# XBEE.net
KiCad netlist of a schematic drawn in Altium Designer
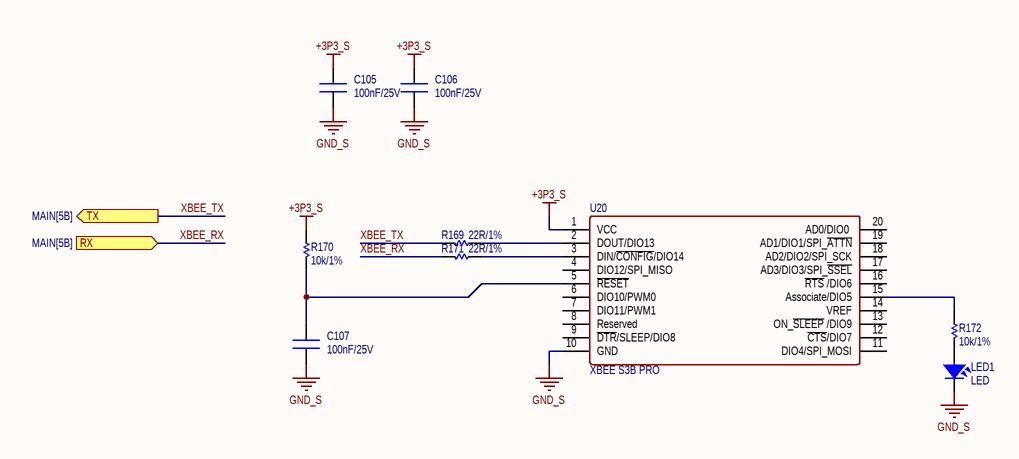
[diagram p0: XBEE.SchDoc]

(export (version "E")
  (design (tool "Eeschema 10.0.6"))
  (components
    (comp (ref "C105")
      (value "100nF/25V")
      (footprint "CN-SMD-0603")
      (description "CAP CER 0.1UF 25V X7R 0603")
      (libsource (lib "Library") (part "CN"))
    )
    (comp (ref "C106")
      (value "100nF/25V")
      (footprint "CN-SMD-0603")
      (description "CAP CER 0.1UF 25V X7R 0603")
      (libsource (lib "Library") (part "CN"))
    )
    (comp (ref "C107")
      (value "100nF/25V")
      (footprint "CN-SMD-0603")
      (description "CAP CER 0.1UF 25V X7R 0603")
      (libsource (lib "Library") (part "CN"))
    )
    (comp (ref "LED1")
      (value "LED")
      (footprint "LED-0603-RED")
      (description "LED RED CLEAR 0603 SMD")
      (libsource (lib "Library") (part "LED SMD"))
    )
    (comp (ref "R169")
      (value "22R/1%")
      (footprint "RES-SMD-0603")
      (description "RES SMD 22 OHM 1% 1/10W 0603")
      (libsource (lib "Library") (part "Res-SMD"))
    )
    (comp (ref "R170")
      (value "10k/1%")
      (footprint "RES-SMD-0603")
      (description "RES SMD 10K OHM 1% 1/10W 0603")
      (fields
        (field (name "MANUFACTURER") "Generic Components")
        (field (name "PUBLISHER") "Altium Hobart Technology Centre")
      )
      (libsource (lib "Library") (part "Res-SMD"))
    )
    (comp (ref "R171")
      (value "22R/1%")
      (footprint "RES-SMD-0603")
      (description "RES SMD 22 OHM 1% 1/10W 0603")
      (libsource (lib "Library") (part "Res-SMD"))
    )
    (comp (ref "R172")
      (value "10k/1%")
      (footprint "RES-SMD-0603")
      (description "RES SMD 10K OHM 1% 1/10W 0603")
      (fields
        (field (name "MANUFACTURER") "Generic Components")
        (field (name "PUBLISHER") "Altium Hobart Technology Centre")
      )
      (libsource (lib "Library") (part "Res-SMD"))
    )
    (comp (ref "U20")
      (value "XBEE S3B PRO")
      (footprint "XBEE S3B PRO DIP")
      (libsource (lib "Library") (part "XBEE S3B PRO"))
    )
  )
  (nets
    (net (code "1") (name "+3P3_S") (class "Default")
      (node (ref "C105") (pin "2") (pinfunction "2_2") (pintype "passive"))
      (node (ref "C106") (pin "2") (pinfunction "2_2") (pintype "passive"))
      (node (ref "R170") (pin "1") (pinfunction "1_1") (pintype "passive"))
      (node (ref "U20") (pin "1") (pinfunction "VCC_1") (pintype "passive"))
    )
    (net (code "2") (name "/XBEE_RX") (class "Default")
      (node (ref "R171") (pin "2") (pinfunction "2_2") (pintype "passive"))
    )
    (net (code "3") (name "/XBEE_TX") (class "Default")
      (node (ref "R169") (pin "2") (pinfunction "2_2") (pintype "passive"))
    )
    (net (code "4") (name "GND_S") (class "Default")
      (node (ref "C105") (pin "1") (pinfunction "1_1") (pintype "passive"))
      (node (ref "C106") (pin "1") (pinfunction "1_1") (pintype "passive"))
      (node (ref "C107") (pin "1") (pinfunction "1_1") (pintype "passive"))
      (node (ref "LED1") (pin "2") (pinfunction "2_2") (pintype "passive"))
      (node (ref "U20") (pin "10") (pinfunction "GND_10") (pintype "passive"))
    )
    (net (code "5") (name "Net-(LED1-Pad1)") (class "Default")
      (node (ref "LED1") (pin "1") (pinfunction "1_1") (pintype "passive"))
      (node (ref "R172") (pin "2") (pinfunction "2_2") (pintype "passive"))
    )
    (net (code "6") (name "Net-(U20-Associate{slash}DIO5)") (class "Default")
      (node (ref "R172") (pin "1") (pinfunction "1_1") (pintype "passive"))
      (node (ref "U20") (pin "15") (pinfunction "Associate/DIO5_15") (pintype "passive"))
    )
    (net (code "7") (name "Net-(U20-DIN{slash}~{CONFIG}{slash}DIO14)") (class "Default")
      (node (ref "R171") (pin "1") (pinfunction "1_1") (pintype "passive"))
      (node (ref "U20") (pin "3") (pinfunction "DIN/~{CONFIG}/DIO14_3") (pintype "passive"))
    )
    (net (code "8") (name "Net-(U20-DOUT{slash}DIO13)") (class "Default")
      (node (ref "R169") (pin "1") (pinfunction "1_1") (pintype "passive"))
      (node (ref "U20") (pin "2") (pinfunction "DOUT/DIO13_2") (pintype "passive"))
    )
    (net (code "9") (name "Net-(U20-~{RESET})") (class "Default")
      (node (ref "C107") (pin "2") (pinfunction "2_2") (pintype "passive"))
      (node (ref "R170") (pin "2") (pinfunction "2_2") (pintype "passive"))
      (node (ref "U20") (pin "5") (pinfunction "~{RESET}_5") (pintype "passive"))
    )
    (net (code "10") (name "unconnected-(U20-AD0{slash}DIO0-Pad20)") (class "Default")
      (node (ref "U20") (pin "20") (pinfunction "AD0/DIO0_20") (pintype "passive"))
    )
    (net (code "11") (name "unconnected-(U20-AD1{slash}DIO1{slash}SPI_~{ATTN}-Pad19)") (class "Default")
      (node (ref "U20") (pin "19") (pinfunction "AD1/DIO1/SPI_~{ATTN}_19") (pintype "passive"))
    )
    (net (code "12") (name "unconnected-(U20-AD2{slash}DIO2{slash}SPI_SCK-Pad18)") (class "Default")
      (node (ref "U20") (pin "18") (pinfunction "AD2/DIO2/SPI_SCK_18") (pintype "passive"))
    )
    (net (code "13") (name "unconnected-(U20-AD3{slash}DIO3{slash}SPI_~{SSEL}-Pad17)") (class "Default")
      (node (ref "U20") (pin "17") (pinfunction "AD3/DIO3/SPI_~{SSEL}_17") (pintype "passive"))
    )
    (net (code "14") (name "unconnected-(U20-DIO4{slash}SPI_MOSI-Pad11)") (class "Default")
      (node (ref "U20") (pin "11") (pinfunction "DIO4/SPI_MOSI_11") (pintype "passive"))
    )
    (net (code "15") (name "unconnected-(U20-DIO10{slash}PWM0-Pad6)") (class "Default")
      (node (ref "U20") (pin "6") (pinfunction "DIO10/PWM0_6") (pintype "passive"))
    )
    (net (code "16") (name "unconnected-(U20-DIO11{slash}PWM1-Pad7)") (class "Default")
      (node (ref "U20") (pin "7") (pinfunction "DIO11/PWM1_7") (pintype "passive"))
    )
    (net (code "17") (name "unconnected-(U20-DIO12{slash}SPI_MISO-Pad4)") (class "Default")
      (node (ref "U20") (pin "4") (pinfunction "DIO12/SPI_MISO_4") (pintype "passive"))
    )
    (net (code "18") (name "unconnected-(U20-ON_~{SLEEP}_{slash}DIO9-Pad13)") (class "Default")
      (node (ref "U20") (pin "13") (pinfunction "ON_~{SLEEP}_/DIO9_13") (pintype "passive"))
    )
    (net (code "19") (name "unconnected-(U20-Reserved-Pad8)") (class "Default")
      (node (ref "U20") (pin "8") (pinfunction "Reserved_8") (pintype "passive"))
    )
    (net (code "20") (name "unconnected-(U20-VREF-Pad14)") (class "Default")
      (node (ref "U20") (pin "14") (pinfunction "VREF_14") (pintype "passive"))
    )
    (net (code "21") (name "unconnected-(U20-~{CTS}{slash}DIO7-Pad12)") (class "Default")
      (node (ref "U20") (pin "12") (pinfunction "~{CTS}/DIO7_12") (pintype "passive"))
    )
    (net (code "22") (name "unconnected-(U20-~{DTR}{slash}SLEEP{slash}DIO8-Pad9)") (class "Default")
      (node (ref "U20") (pin "9") (pinfunction "~{DTR}/SLEEP/DIO8_9") (pintype "passive"))
    )
    (net (code "23") (name "unconnected-(U20-~{RTS}_{slash}DIO6-Pad16)") (class "Default")
      (node (ref "U20") (pin "16") (pinfunction "~{RTS}_/DIO6_16") (pintype "passive"))
    )
  )
)
